# NodeMCU-Gateway-NRF.net
KiCad netlist of a schematic drawn in EAGLE
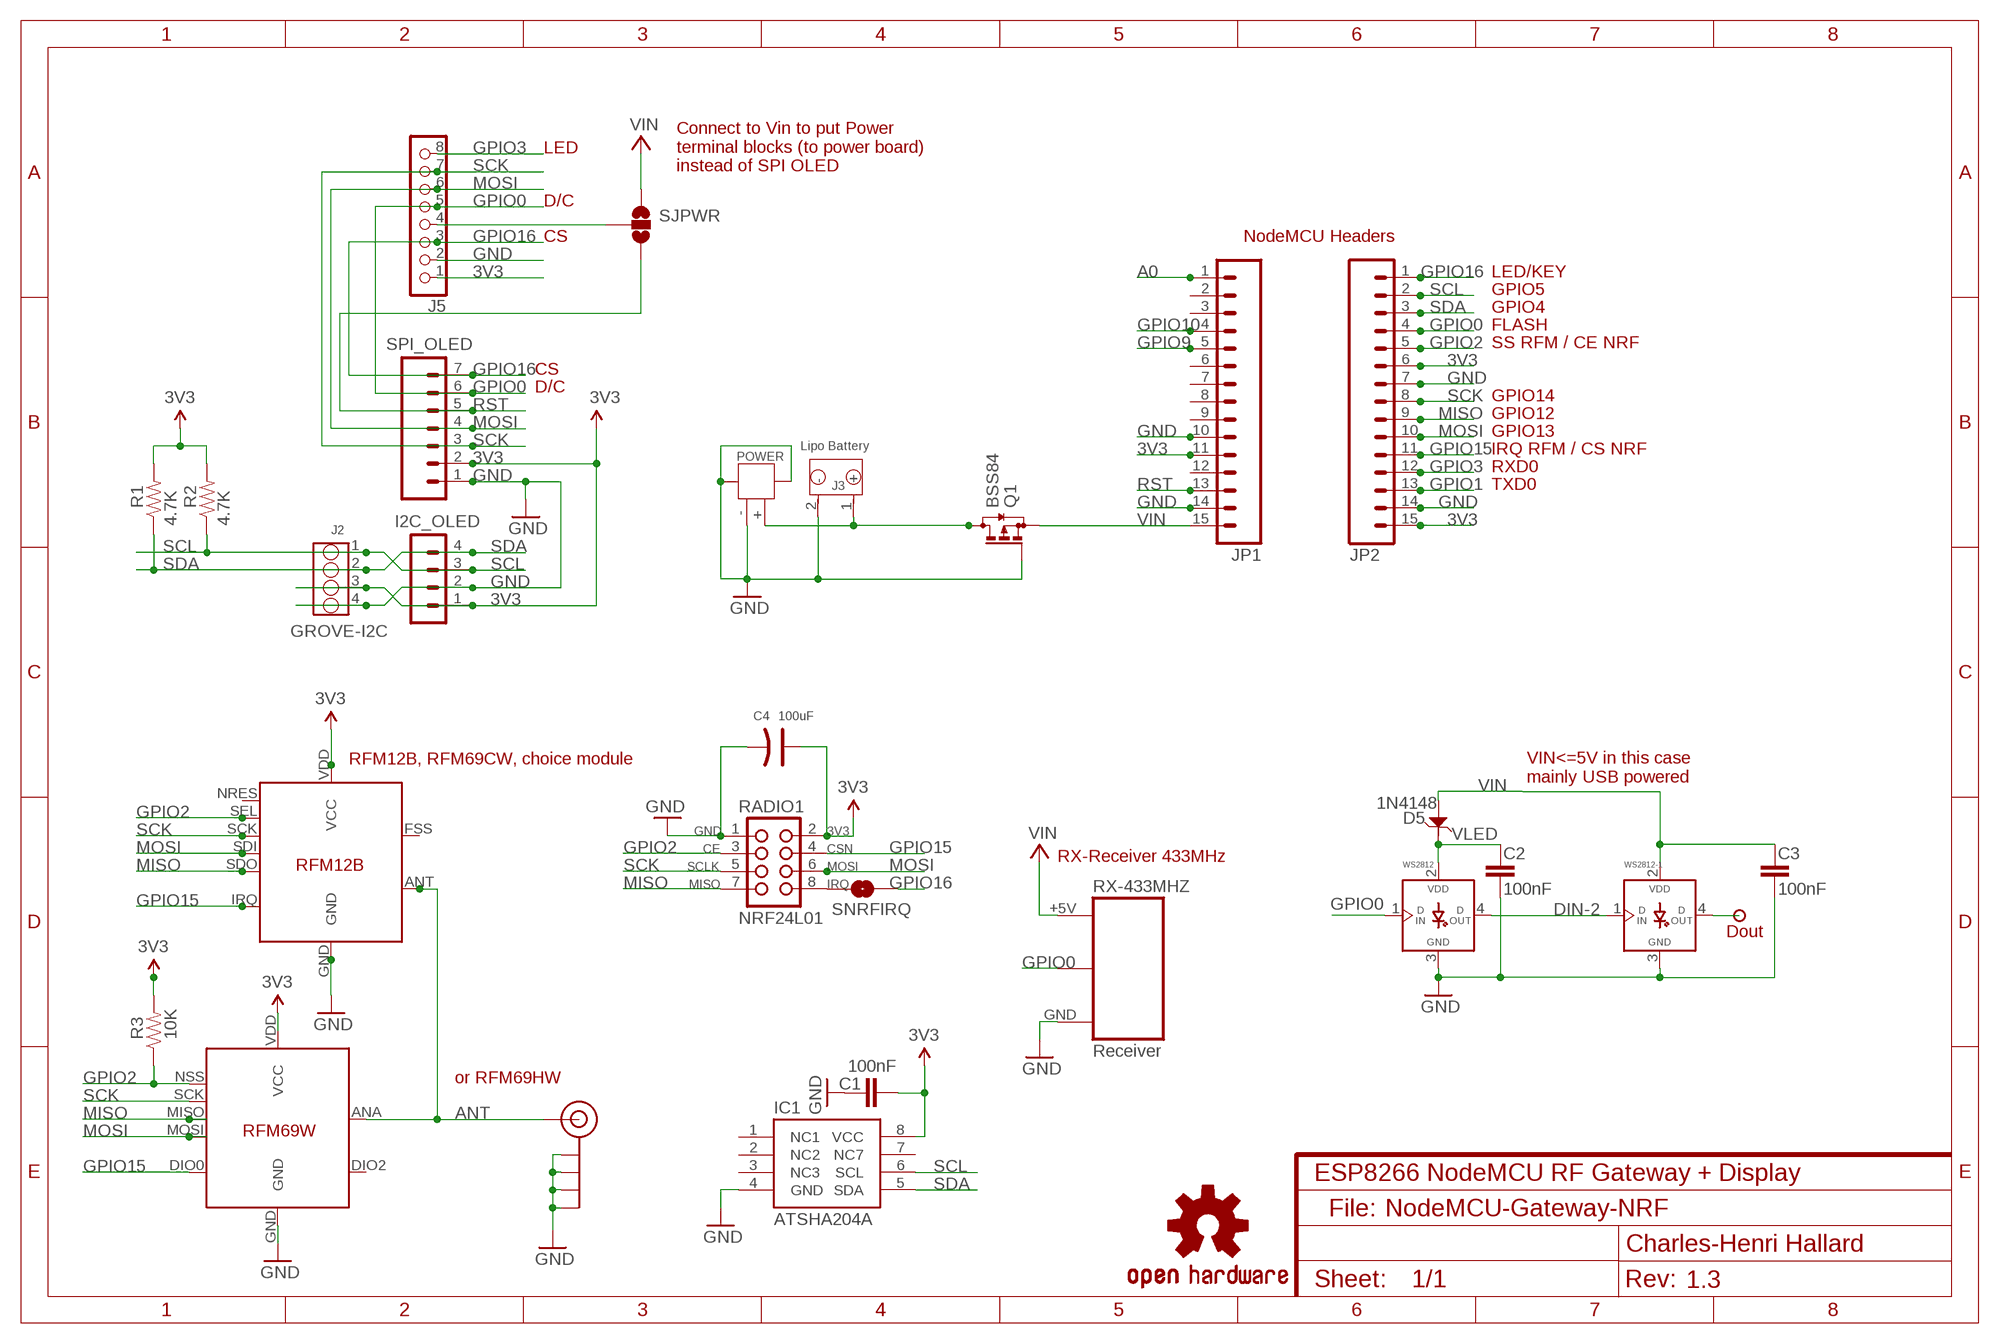
[diagram p0: schematic, sheet 1]

(export (version "E")
  (design (tool "Eeschema 10.0.6"))
  (components
    (comp (ref "C1")
      (value "100nF")
      (footprint "eagle-import:0805-CAP")
      (libsource (lib "eagle-import") (part "CAP0805-CAP"))
    )
    (comp (ref "C2")
      (value "100nF")
      (footprint "eagle-import:0805-CAP")
      (libsource (lib "eagle-import") (part "CAP0805-CAP"))
    )
    (comp (ref "C3")
      (value "100nF")
      (footprint "eagle-import:0805-CAP")
      (libsource (lib "eagle-import") (part "CAP0805-CAP"))
    )
    (comp (ref "C4")
      (value "100uF")
      (footprint "eagle-import:RADIAL-2.0-D5.0_H7MM")
      (libsource (lib "eagle-import") (part "CAP-POLAR-D5.3/2.0"))
    )
    (comp (ref "D5")
      (value "1N4148")
      (footprint "eagle-import:SOD123-2.7X1.6")
      (libsource (lib "eagle-import") (part "D-ESD-2P-CESD5V0D1"))
    )
    (comp (ref "I2C_OLED")
      (value "CON_HEADER_1X04'LOCK'")
      (footprint "eagle-import:1X04_LOCK")
      (libsource (lib "eagle-import") (part "CON_HEADER_1X04'LOCK'"))
    )
    (comp (ref "IC1")
      (value "ATSHA204A")
      (footprint "eagle-import:SOIC8")
      (libsource (lib "eagle-import") (part "ATSHA204_SOIC8"))
    )
    (comp (ref "J$2")
      (value "ANTENNATINY")
      (footprint "eagle-import:SMA_UFL_PAD_TINY")
      (libsource (lib "eagle-import") (part "ANTENNATINY"))
    )
    (comp (ref "J2")
      (value "GROVE-I2C")
      (footprint "eagle-import:4P-2.0-90D")
      (libsource (lib "eagle-import") (part "GROVE-4P-2.0-3470140P1"))
    )
    (comp (ref "J3")
      (value "Lipo Battery")
      (footprint "eagle-import:2P-2.0-90D")
      (libsource (lib "eagle-import") (part "JST-2P-PW-3410070P1"))
    )
    (comp (ref "J5")
      (value "CON_HEADER_1X08-PTH")
      (footprint "eagle-import:M1X8")
      (libsource (lib "eagle-import") (part "CON_HEADER_1X08-PTH"))
    )
    (comp (ref "JP1")
      (value "M15LOCK")
      (footprint "eagle-import:1X15_LOCK")
      (libsource (lib "eagle-import") (part "M15LOCK"))
    )
    (comp (ref "JP2")
      (value "M15LOCK")
      (footprint "eagle-import:1X15_LOCK")
      (libsource (lib "eagle-import") (part "M15LOCK"))
    )
    (comp (ref "LOGO2")
      (value "OSHW-LOGOL")
      (footprint "eagle-import:OSHW-LOGO-L")
      (libsource (lib "eagle-import") (part "OSHW-LOGOL"))
    )
    (comp (ref "P2")
      (value "PADNORMAL")
      (footprint "eagle-import:PAD")
      (libsource (lib "eagle-import") (part "PADNORMAL"))
    )
    (comp (ref "POWER")
      (value "JST-2P-SMD'2.0'")
      (footprint "eagle-import:2P-SMD-2.0-90D")
      (libsource (lib "eagle-import") (part "JST-2P-SMD'2.0'"))
    )
    (comp (ref "Q1")
      (value "BSS84")
      (footprint "eagle-import:SOT23")
      (libsource (lib "eagle-import") (part "BSS84"))
    )
    (comp (ref "R1")
      (value "4.7K")
      (footprint "eagle-import:0805-RES")
      (libsource (lib "eagle-import") (part "RESISTOR0805-RES"))
    )
    (comp (ref "R2")
      (value "4.7K")
      (footprint "eagle-import:0805-RES")
      (libsource (lib "eagle-import") (part "RESISTOR0805-RES"))
    )
    (comp (ref "R3")
      (value "10K")
      (footprint "eagle-import:0805-RES")
      (libsource (lib "eagle-import") (part "RESISTOR0805-RES"))
    )
    (comp (ref "RADIO1")
      (value "NRF24L01")
      (footprint "eagle-import:2X04_NO_LOCK")
      (libsource (lib "eagle-import") (part "NRF24L01"))
    )
    (comp (ref "RX-433MHZ")
      (value "Receiver")
      (footprint "eagle-import:RF-LINK_RX_NO_SILK")
      (libsource (lib "eagle-import") (part "RF-LINK_RX"))
    )
    (comp (ref "SJPWR")
      (value "JUMPER-PAD-3-2OF3_NC_BY_TRACE_LARGE")
      (footprint "eagle-import:PAD-JUMPER-3-2OF3_NC_BY_TRACE_YES_SILK_LARGE")
      (libsource (lib "eagle-import") (part "JUMPER-PAD-3-2OF3_NC_BY_TRACE_LARGE"))
    )
    (comp (ref "SNRFIRQ")
      (value "NRFIRQ")
      (footprint "eagle-import:PAD-JUMPER-2-NO_YES_SILK")
      (libsource (lib "eagle-import") (part "JUMPER-PAD-2-NOYES_SILK"))
    )
    (comp (ref "SPI_OLED")
      (value "CON_HEADER_1X07'SMALL'")
      (footprint "eagle-import:M1X7")
      (libsource (lib "eagle-import") (part "CON_HEADER_1X07'SMALL'"))
    )
    (comp (ref "U$2")
      (value "RFM12B")
      (footprint "eagle-import:RFM12B-MINPADS")
      (libsource (lib "eagle-import") (part "RFM12B"))
    )
    (comp (ref "U$3")
      (value "RFM69W")
      (footprint "eagle-import:RFM69W-MINPADS")
      (libsource (lib "eagle-import") (part "RFM69W"))
    )
    (comp (ref "WS2812")
      (value "WS2812B")
      (footprint "eagle-import:WS2812-PTH")
      (libsource (lib "eagle-import") (part "WS2812B5MM"))
    )
    (comp (ref "WS2812-1")
      (value "WS2812B")
      (footprint "eagle-import:WS2812-PTH")
      (libsource (lib "eagle-import") (part "WS2812B5MM"))
    )
  )
  (nets
    (net (code "1") (name "/A0") (class "Default")
      (node (ref "JP1") (pin "1") (pinfunction "1_1") (pintype "passive"))
    )
    (net (code "2") (name "/ANT") (class "Default")
      (node (ref "J$2") (pin "ANT1") (pinfunction "SIGNAL_ANT1") (pintype "bidirectional"))
      (node (ref "J$2") (pin "ANT2") (pinfunction "SIGNAL_ANT2") (pintype "bidirectional"))
      (node (ref "J$2") (pin "ANT3") (pinfunction "SIGNAL_ANT3") (pintype "bidirectional"))
      (node (ref "U$2") (pin "ANT") (pinfunction "ANT_ANT") (pintype "passive"))
      (node (ref "U$3") (pin "ANA") (pinfunction "ANT_ANA") (pintype "passive"))
    )
    (net (code "3") (name "/DIN-2") (class "Default")
      (node (ref "WS2812") (pin "4") (pinfunction "DOUT_4") (pintype "output"))
      (node (ref "WS2812-1") (pin "1") (pinfunction "DIN_1") (pintype "input"))
    )
    (net (code "4") (name "/GPIO0") (class "Default")
      (node (ref "J5") (pin "5") (pinfunction "5_5") (pintype "passive"))
      (node (ref "JP2") (pin "4") (pinfunction "4_4") (pintype "passive"))
      (node (ref "RX-433MHZ") (pin "DATA@1") (pinfunction "DATA_DATA@1") (pintype "output"))
      (node (ref "RX-433MHZ") (pin "DATA@2") (pinfunction "DATA_DATA@2") (pintype "output"))
      (node (ref "SPI_OLED") (pin "6") (pinfunction "6_6") (pintype "passive"))
      (node (ref "WS2812") (pin "1") (pinfunction "DIN_1") (pintype "input"))
    )
    (net (code "5") (name "/GPIO1") (class "Default")
      (node (ref "JP2") (pin "13") (pinfunction "13_13") (pintype "passive"))
    )
    (net (code "6") (name "/GPIO2") (class "Default")
      (node (ref "JP2") (pin "5") (pinfunction "5_5") (pintype "passive"))
      (node (ref "R3") (pin "1") (pinfunction "1_1") (pintype "passive"))
      (node (ref "RADIO1") (pin "3") (pinfunction "CE_3") (pintype "input"))
      (node (ref "U$2") (pin "SEL") (pinfunction "SEL_SEL") (pintype "input"))
      (node (ref "U$3") (pin "NSS") (pinfunction "SEL_NSS") (pintype "input"))
    )
    (net (code "7") (name "/GPIO3") (class "Default")
      (node (ref "J5") (pin "8") (pinfunction "8_8") (pintype "passive"))
      (node (ref "JP2") (pin "12") (pinfunction "12_12") (pintype "passive"))
    )
    (net (code "8") (name "/GPIO9") (class "Default")
      (node (ref "JP1") (pin "5") (pinfunction "5_5") (pintype "passive"))
    )
    (net (code "9") (name "/GPIO10") (class "Default")
      (node (ref "JP1") (pin "4") (pinfunction "4_4") (pintype "passive"))
    )
    (net (code "10") (name "/GPIO15") (class "Default")
      (node (ref "JP2") (pin "11") (pinfunction "11_11") (pintype "passive"))
      (node (ref "RADIO1") (pin "4") (pinfunction "CSN_4") (pintype "input"))
      (node (ref "U$2") (pin "IRQ") (pinfunction "IRQ_IRQ") (pintype "open_collector"))
      (node (ref "U$3") (pin "DIO0") (pinfunction "DIO0_DIO0") (pintype "open_collector"))
    )
    (net (code "11") (name "/GPIO16") (class "Default")
      (node (ref "J5") (pin "3") (pinfunction "3_3") (pintype "passive"))
      (node (ref "JP2") (pin "1") (pinfunction "1_1") (pintype "passive"))
      (node (ref "SNRFIRQ") (pin "2") (pinfunction "2_2") (pintype "passive"))
      (node (ref "SPI_OLED") (pin "7") (pinfunction "7_7") (pintype "passive"))
    )
    (net (code "12") (name "/MISO") (class "Default")
      (node (ref "JP2") (pin "9") (pinfunction "9_9") (pintype "passive"))
      (node (ref "RADIO1") (pin "7") (pinfunction "MISO_7") (pintype "output"))
      (node (ref "U$2") (pin "SDO") (pinfunction "SDO_SDO") (pintype "output"))
      (node (ref "U$3") (pin "MISO") (pinfunction "MISO_MISO") (pintype "input"))
    )
    (net (code "13") (name "/MOSI") (class "Default")
      (node (ref "J5") (pin "6") (pinfunction "6_6") (pintype "passive"))
      (node (ref "JP2") (pin "10") (pinfunction "10_10") (pintype "passive"))
      (node (ref "RADIO1") (pin "6") (pinfunction "MOSI_6") (pintype "input"))
      (node (ref "SPI_OLED") (pin "4") (pinfunction "4_4") (pintype "passive"))
      (node (ref "U$2") (pin "SDI") (pinfunction "SDI_SDI") (pintype "input"))
      (node (ref "U$3") (pin "MOSI") (pinfunction "MOSI_MOSI") (pintype "output"))
    )
    (net (code "14") (name "/RST") (class "Default")
      (node (ref "JP1") (pin "13") (pinfunction "13_13") (pintype "passive"))
      (node (ref "SJPWR") (pin "3") (pinfunction "3_3") (pintype "passive"))
      (node (ref "SPI_OLED") (pin "5") (pinfunction "5_5") (pintype "passive"))
    )
    (net (code "15") (name "/SCK") (class "Default")
      (node (ref "J5") (pin "7") (pinfunction "7_7") (pintype "passive"))
      (node (ref "JP2") (pin "8") (pinfunction "8_8") (pintype "passive"))
      (node (ref "RADIO1") (pin "5") (pinfunction "CLK_5") (pintype "input"))
      (node (ref "SPI_OLED") (pin "3") (pinfunction "3_3") (pintype "passive"))
      (node (ref "U$2") (pin "SCK") (pinfunction "SCK_SCK") (pintype "input"))
      (node (ref "U$3") (pin "SCK") (pinfunction "SCK_SCK") (pintype "input"))
    )
    (net (code "16") (name "/SCL") (class "Default")
      (node (ref "I2C_OLED") (pin "3") (pinfunction "3_3") (pintype "passive"))
      (node (ref "IC1") (pin "6") (pinfunction "SCL_6") (pintype "bidirectional"))
      (node (ref "J2") (pin "1") (pinfunction "1_1") (pintype "bidirectional"))
      (node (ref "JP2") (pin "2") (pinfunction "2_2") (pintype "passive"))
      (node (ref "R2") (pin "1") (pinfunction "1_1") (pintype "passive"))
    )
    (net (code "17") (name "/SDA") (class "Default")
      (node (ref "I2C_OLED") (pin "4") (pinfunction "4_4") (pintype "passive"))
      (node (ref "IC1") (pin "5") (pinfunction "SDA_5") (pintype "bidirectional"))
      (node (ref "J2") (pin "2") (pinfunction "2_2") (pintype "bidirectional"))
      (node (ref "JP2") (pin "3") (pinfunction "3_3") (pintype "passive"))
      (node (ref "R1") (pin "1") (pinfunction "1_1") (pintype "passive"))
    )
    (net (code "18") (name "/VLED") (class "Default")
      (node (ref "C2") (pin "2") (pinfunction "2_2") (pintype "passive"))
      (node (ref "D5") (pin "2") (pinfunction "2_2") (pintype "bidirectional"))
      (node (ref "WS2812") (pin "2") (pinfunction "VDD_2") (pintype "power_in"))
    )
    (net (code "19") (name "3V3") (class "Default")
      (node (ref "C1") (pin "2") (pinfunction "2_2") (pintype "passive"))
      (node (ref "C4") (pin "+") (pinfunction "+_+") (pintype "passive"))
      (node (ref "I2C_OLED") (pin "1") (pinfunction "1_1") (pintype "passive"))
      (node (ref "IC1") (pin "8") (pinfunction "VCC_8") (pintype "power_in"))
      (node (ref "J2") (pin "3") (pinfunction "3_3") (pintype "bidirectional"))
      (node (ref "J5") (pin "1") (pinfunction "1_1") (pintype "passive"))
      (node (ref "JP1") (pin "11") (pinfunction "11_11") (pintype "passive"))
      (node (ref "JP2") (pin "15") (pinfunction "15_15") (pintype "passive"))
      (node (ref "JP2") (pin "6") (pinfunction "6_6") (pintype "passive"))
      (node (ref "R1") (pin "2") (pinfunction "2_2") (pintype "passive"))
      (node (ref "R2") (pin "2") (pinfunction "2_2") (pintype "passive"))
      (node (ref "R3") (pin "2") (pinfunction "2_2") (pintype "passive"))
      (node (ref "RADIO1") (pin "2") (pinfunction "3V3_2") (pintype "power_in"))
      (node (ref "SPI_OLED") (pin "2") (pinfunction "2_2") (pintype "passive"))
      (node (ref "U$2") (pin "VDD") (pinfunction "VCC_VDD") (pintype "power_in"))
      (node (ref "U$3") (pin "VDD") (pinfunction "VCC_VDD") (pintype "power_in"))
    )
    (net (code "20") (name "GND") (class "Default")
      (node (ref "C1") (pin "1") (pinfunction "1_1") (pintype "passive"))
      (node (ref "C2") (pin "1") (pinfunction "1_1") (pintype "passive"))
      (node (ref "C3") (pin "1") (pinfunction "1_1") (pintype "passive"))
      (node (ref "C4") (pin "-") (pinfunction "-_-") (pintype "passive"))
      (node (ref "I2C_OLED") (pin "2") (pinfunction "2_2") (pintype "passive"))
      (node (ref "IC1") (pin "4") (pinfunction "GND_4") (pintype "power_in"))
      (node (ref "J$2") (pin "GND1") (pinfunction "GND_GND1") (pintype "bidirectional"))
      (node (ref "J$2") (pin "GND2") (pinfunction "GND_GND2") (pintype "bidirectional"))
      (node (ref "J$2") (pin "GND3") (pinfunction "GND_GND3") (pintype "bidirectional"))
      (node (ref "J$2") (pin "GND4") (pinfunction "GND_GND4") (pintype "bidirectional"))
      (node (ref "J2") (pin "4") (pinfunction "4_4") (pintype "bidirectional"))
      (node (ref "J3") (pin "2") (pinfunction "-_2") (pintype "bidirectional"))
      (node (ref "J5") (pin "2") (pinfunction "2_2") (pintype "passive"))
      (node (ref "JP1") (pin "10") (pinfunction "10_10") (pintype "passive"))
      (node (ref "JP1") (pin "14") (pinfunction "14_14") (pintype "passive"))
      (node (ref "JP2") (pin "14") (pinfunction "14_14") (pintype "passive"))
      (node (ref "JP2") (pin "7") (pinfunction "7_7") (pintype "passive"))
      (node (ref "POWER") (pin "-") (pinfunction "2_-") (pintype "bidirectional"))
      (node (ref "POWER") (pin "3") (pinfunction "3_3") (pintype "bidirectional"))
      (node (ref "POWER") (pin "4") (pinfunction "4_4") (pintype "bidirectional"))
      (node (ref "Q1") (pin "1") (pinfunction "G_1") (pintype "passive"))
      (node (ref "RADIO1") (pin "1") (pinfunction "GND_1") (pintype "passive"))
      (node (ref "RX-433MHZ") (pin "GND") (pinfunction "GND_GND") (pintype "power_in"))
      (node (ref "SPI_OLED") (pin "1") (pinfunction "1_1") (pintype "passive"))
      (node (ref "U$2") (pin "GND") (pinfunction "GND_GND") (pintype "power_in"))
      (node (ref "U$3") (pin "GND") (pinfunction "GND_GND") (pintype "power_in"))
      (node (ref "WS2812") (pin "3") (pinfunction "GND_3") (pintype "power_in"))
      (node (ref "WS2812-1") (pin "3") (pinfunction "GND_3") (pintype "power_in"))
    )
    (net (code "21") (name "Net-(J3-+)") (class "Default")
      (node (ref "J3") (pin "1") (pinfunction "+_1") (pintype "bidirectional"))
      (node (ref "POWER") (pin "+") (pinfunction "1_+") (pintype "bidirectional"))
      (node (ref "Q1") (pin "3") (pinfunction "D_3") (pintype "passive"))
    )
    (net (code "22") (name "Net-(J5-Pad4)") (class "Default")
      (node (ref "J5") (pin "4") (pinfunction "4_4") (pintype "passive"))
      (node (ref "SJPWR") (pin "2") (pinfunction "2_2") (pintype "passive"))
    )
    (net (code "23") (name "Net-(RADIO1-IRQ)") (class "Default")
      (node (ref "RADIO1") (pin "8") (pinfunction "IRQ_8") (pintype "output"))
      (node (ref "SNRFIRQ") (pin "1") (pinfunction "1_1") (pintype "passive"))
    )
    (net (code "24") (name "Net-(WS2812-1-DOUT)") (class "Default")
      (node (ref "P2") (pin "1") (pinfunction "1_1") (pintype "bidirectional"))
      (node (ref "WS2812-1") (pin "4") (pinfunction "DOUT_4") (pintype "output"))
    )
    (net (code "25") (name "VIN") (class "Default")
      (node (ref "C3") (pin "2") (pinfunction "2_2") (pintype "passive"))
      (node (ref "D5") (pin "1") (pinfunction "1_1") (pintype "bidirectional"))
      (node (ref "JP1") (pin "15") (pinfunction "15_15") (pintype "passive"))
      (node (ref "Q1") (pin "2") (pinfunction "S_2") (pintype "passive"))
      (node (ref "RX-433MHZ") (pin "+5V") (pinfunction "+5V_+5V") (pintype "power_in"))
      (node (ref "SJPWR") (pin "1") (pinfunction "1_1") (pintype "passive"))
      (node (ref "WS2812-1") (pin "2") (pinfunction "VDD_2") (pintype "power_in"))
    )
    (net (code "26") (name "unconnected-(IC1-NC1-Pad1)") (class "Default")
      (node (ref "IC1") (pin "1") (pinfunction "NC1_1") (pintype "no_connect"))
    )
    (net (code "27") (name "unconnected-(IC1-NC2-Pad2)") (class "Default")
      (node (ref "IC1") (pin "2") (pinfunction "NC2_2") (pintype "no_connect"))
    )
    (net (code "28") (name "unconnected-(IC1-NC3-Pad3)") (class "Default")
      (node (ref "IC1") (pin "3") (pinfunction "NC3_3") (pintype "no_connect"))
    )
    (net (code "29") (name "unconnected-(IC1-NC7-Pad7)") (class "Default")
      (node (ref "IC1") (pin "7") (pinfunction "NC7_7") (pintype "no_connect"))
    )
    (net (code "30") (name "unconnected-(JP1-Pad2)") (class "Default")
      (node (ref "JP1") (pin "2") (pinfunction "2_2") (pintype "passive"))
    )
    (net (code "31") (name "unconnected-(JP1-Pad3)") (class "Default")
      (node (ref "JP1") (pin "3") (pinfunction "3_3") (pintype "passive"))
    )
    (net (code "32") (name "unconnected-(JP1-Pad6)") (class "Default")
      (node (ref "JP1") (pin "6") (pinfunction "6_6") (pintype "passive"))
    )
    (net (code "33") (name "unconnected-(JP1-Pad7)") (class "Default")
      (node (ref "JP1") (pin "7") (pinfunction "7_7") (pintype "passive"))
    )
    (net (code "34") (name "unconnected-(JP1-Pad8)") (class "Default")
      (node (ref "JP1") (pin "8") (pinfunction "8_8") (pintype "passive"))
    )
    (net (code "35") (name "unconnected-(JP1-Pad9)") (class "Default")
      (node (ref "JP1") (pin "9") (pinfunction "9_9") (pintype "passive"))
    )
    (net (code "36") (name "unconnected-(JP1-Pad12)") (class "Default")
      (node (ref "JP1") (pin "12") (pinfunction "12_12") (pintype "passive"))
    )
    (net (code "37") (name "unconnected-(U$2-FFS-PadFSS)") (class "Default")
      (node (ref "U$2") (pin "FSS") (pinfunction "FFS_FSS") (pintype "bidirectional"))
    )
    (net (code "38") (name "unconnected-(U$2-PadNRES)") (class "Default")
      (node (ref "U$2") (pin "NRES") (pinfunction "NRES_NRES") (pintype "input"))
    )
    (net (code "39") (name "unconnected-(U$3-PadDIO2)") (class "Default")
      (node (ref "U$3") (pin "DIO2") (pinfunction "DIO2_DIO2") (pintype "open_collector"))
    )
  )
)
